# LNA.net
KiCad netlist of a schematic drawn in Altium Designer
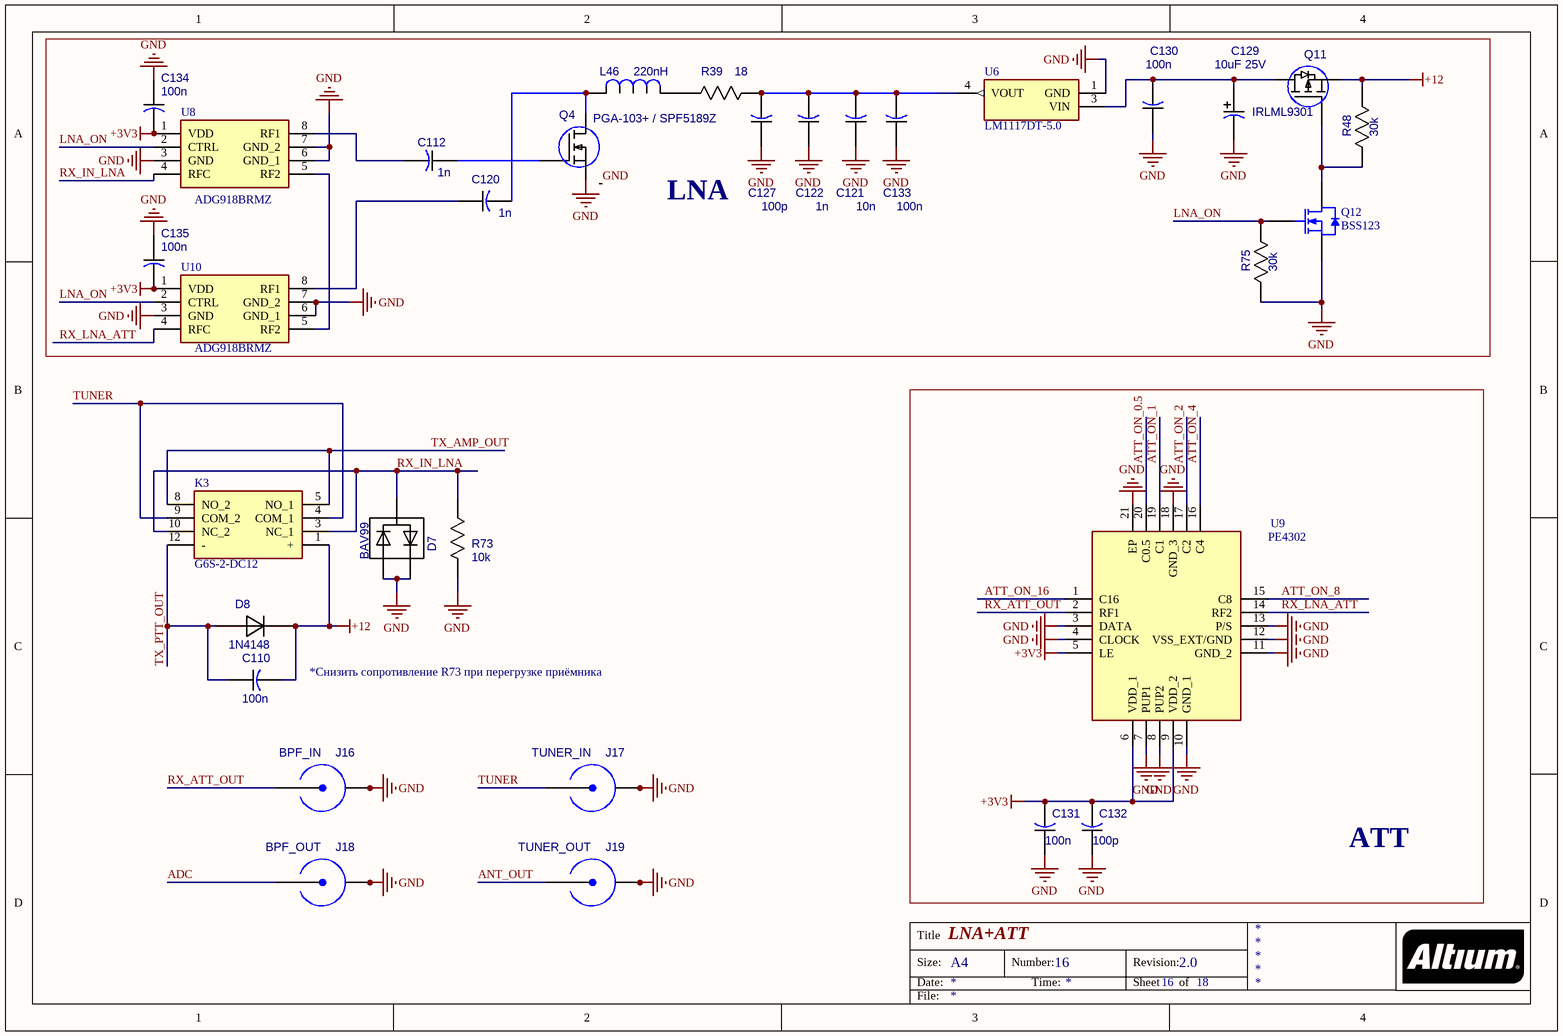
[diagram p0: LNA.SchDoc]

(export (version "E")
  (design (tool "Eeschema 10.0.6"))
  (components
    (comp (ref "C110")
      (value "100n")
      (footprint "CAP_0805")
      (description "CAP_0805")
      (libsource (lib "*") (part "CAP_0805"))
    )
    (comp (ref "C112")
      (value "1n")
      (footprint "CAP_0805")
      (description "CAP_0805")
      (libsource (lib "*") (part "CAP_0805"))
    )
    (comp (ref "C120")
      (value "1n")
      (footprint "CAP_0805")
      (description "CAP_0805")
      (libsource (lib "*") (part "CAP_0805"))
    )
    (comp (ref "C121")
      (value "10n")
      (footprint "6-0805_M")
      (description "CAP_0805")
      (libsource (lib "*") (part "CAP_0805"))
    )
    (comp (ref "C122")
      (value "1n")
      (footprint "6-0805_M")
      (description "CAP_0805")
      (libsource (lib "*") (part "CAP_0805"))
    )
    (comp (ref "C127")
      (value "100p")
      (footprint "6-0805_M")
      (description "CAP_0805")
      (libsource (lib "*") (part "CAP_0805"))
    )
    (comp (ref "C129")
      (value "10uF 25V")
      (footprint "CAPAE_5.3x5.3h6.1")
      (description "CAPAE_5.3x5.3h6.1")
      (libsource (lib "*") (part "CAPAE_5.3x5.3h6.1"))
    )
    (comp (ref "C130")
      (value "100n")
      (footprint "CAP_0805")
      (description "CAP_0805")
      (libsource (lib "") (part "CAP_0805_1"))
    )
    (comp (ref "C131")
      (value "100n")
      (footprint "6-0805_M")
      (description "CAP_0805")
      (libsource (lib "*") (part "CAP_0805"))
    )
    (comp (ref "C132")
      (value "100p")
      (footprint "6-0805_M")
      (description "CAP_0805")
      (libsource (lib "*") (part "CAP_0805"))
    )
    (comp (ref "C133")
      (value "100n")
      (footprint "CAP_0805")
      (description "CAP_0805")
      (libsource (lib "*") (part "CAP_0805"))
    )
    (comp (ref "C134")
      (value "100n")
      (footprint "CAP_0805")
      (description "CAP_0805")
      (libsource (lib "*") (part "CAP_0805"))
    )
    (comp (ref "C135")
      (value "100n")
      (footprint "CAP_0805")
      (description "CAP_0805")
      (libsource (lib "*") (part "CAP_0805"))
    )
    (comp (ref "D7") (value "BAV99") (footprint "SOT23") (libsource (lib "*") (part "BAV99")))
    (comp (ref "D8") (value "1N4148") (footprint "SS14") (libsource (lib "RF-UNIT-BIG") (part "1N4148")))
    (comp (ref "J16")
      (value "BPF_IN")
      (footprint "31-5431")
      (description "SMA")
      (libsource (lib "RF-UNIT_1") (part "31-5431"))
    )
    (comp (ref "J17")
      (value "TUNER_IN")
      (footprint "31-5431")
      (description "SMA")
      (libsource (lib "RF-UNIT_1") (part "31-5431"))
    )
    (comp (ref "J18")
      (value "BPF_OUT")
      (footprint "31-5431")
      (description "SMA")
      (libsource (lib "RF-UNIT_1") (part "31-5431"))
    )
    (comp (ref "J19")
      (value "TUNER_OUT")
      (footprint "31-5431")
      (description "SMA")
      (libsource (lib "RF-UNIT_1") (part "31-5431"))
    )
    (comp (ref "K3")
      (value "G6S-2-DC12")
      (footprint "G6S2DC12")
      (description "Relay or Contactor")
      (fields (field (name "MOUSER PART NUMBER") "653-G6S-2-DC12A"))
      (libsource (lib "*") (part "G6S-2-DC12"))
    )
    (comp (ref "L46")
      (value "220nH")
      (footprint "IND_1206")
      (description "IND_1206")
      (libsource (lib "*") (part "IND_1206"))
    )
    (comp (ref "Q4")
      (value "PGA-103+ / SPF5189Z")
      (footprint "SOT89")
      (libsource (lib "*") (part "PGA-103+"))
    )
    (comp (ref "Q11")
      (value "IRLML9301")
      (footprint "SOT23")
      (description "MOSFET")
      (libsource (lib "*") (part "MOSFET_ENH_PD"))
    )
    (comp (ref "Q12")
      (value "BSS123")
      (footprint "FAIR-SOT23-3_V")
      (fields (field (name "MANUFACTURER") "Fairchild"))
      (libsource (lib "Altium Content Vault") (part "NEMOS-GSD-3"))
    )
    (comp (ref "R39")
      (value "18")
      (footprint "RES_1206")
      (description "RES_1206")
      (libsource (lib "*") (part "RES_1206"))
    )
    (comp (ref "R48")
      (value "30k")
      (footprint "RES_0805")
      (description "RES_0805")
      (libsource (lib "*") (part "RES_0805"))
    )
    (comp (ref "R73")
      (value "10k")
      (footprint "RES_1206")
      (description "RES_1206")
      (libsource (lib "*") (part "RES_1206"))
    )
    (comp (ref "R75")
      (value "30k")
      (footprint "RES_0805")
      (description "RES_0805")
      (libsource (lib "*") (part "RES_0805"))
    )
    (comp (ref "U6")
      (value "LM1117DT-5.0")
      (footprint "SamacSys:TO228P991X238-3N")
      (description "Integrated Circuit")
      (fields
        (field (name "MANUFACTURER_PART_NUMBER") "LM1117DT-ADJ")
        (field (name "MOUSER PART NUMBER") "926-LM1117DT-ADJ")
      )
      (libsource (lib "*") (part "LM1117DT-ADJ"))
    )
    (comp (ref "U8")
      (value "ADG918BRMZ")
      (footprint "SOP65P490X110-8N")
      (description "Integrated Circuit")
      (fields (field (name "MOUSER PART NUMBER") "584-ADG918BRMZ") (field (name "RS PART NUMBER") "4969212P"))
      (libsource (lib "RF-UNIT-BIG") (part "ADG918BRMZ"))
    )
    (comp (ref "U9")
      (value "PE4302")
      (footprint "QFN50P400X400X90-21N")
      (description "Integrated Circuit")
      (fields (field (name "MANUFACTURER_PART_NUMBER") "PE4312C-Z"))
      (libsource (lib "RF-UNIT-BIG") (part "PE4312C-Z"))
    )
    (comp (ref "U10")
      (value "ADG918BRMZ")
      (footprint "SOP65P490X110-8N")
      (description "Integrated Circuit")
      (fields (field (name "MOUSER PART NUMBER") "584-ADG918BRMZ") (field (name "RS PART NUMBER") "4969212P"))
      (libsource (lib "RF-UNIT-BIG") (part "ADG918BRMZ"))
    )
  )
  (nets
    (net (code "1") (name "+3V3") (class "Default")
      (node (ref "C131") (pin "2") (pinfunction "2_2") (pintype "passive"))
      (node (ref "C132") (pin "2") (pinfunction "2_2") (pintype "passive"))
      (node (ref "C134") (pin "2") (pinfunction "2_2") (pintype "passive"))
      (node (ref "C135") (pin "2") (pinfunction "2_2") (pintype "passive"))
      (node (ref "U10") (pin "1") (pinfunction "VDD_1") (pintype "power_in"))
      (node (ref "U8") (pin "1") (pinfunction "VDD_1") (pintype "power_in"))
      (node (ref "U9") (pin "5") (pinfunction "LE_5") (pintype "passive"))
      (node (ref "U9") (pin "6") (pinfunction "VDD_1_6") (pintype "passive"))
      (node (ref "U9") (pin "9") (pinfunction "VDD_2_9") (pintype "passive"))
    )
    (net (code "2") (name "+12") (class "Default")
      (node (ref "C110") (pin "2") (pinfunction "2_2") (pintype "passive"))
      (node (ref "D8") (pin "1") (pinfunction "K_1") (pintype "passive"))
      (node (ref "K3") (pin "1") (pinfunction "+_1") (pintype "passive"))
      (node (ref "Q11") (pin "2") (pinfunction "S_2") (pintype "passive"))
      (node (ref "R48") (pin "2") (pinfunction "2_2") (pintype "passive"))
    )
    (net (code "3") (name "/ADC") (class "Default")
      (node (ref "J18") (pin "5") (pinfunction "CON_5") (pintype "passive"))
    )
    (net (code "4") (name "/ANT_OUT") (class "Default")
      (node (ref "J19") (pin "5") (pinfunction "CON_5") (pintype "passive"))
    )
    (net (code "5") (name "/ATT_ON_0.5") (class "Default")
      (node (ref "U9") (pin "20") (pinfunction "C0.5_20") (pintype "passive"))
    )
    (net (code "6") (name "/ATT_ON_1") (class "Default")
      (node (ref "U9") (pin "19") (pinfunction "C1_19") (pintype "passive"))
    )
    (net (code "7") (name "/ATT_ON_2") (class "Default")
      (node (ref "U9") (pin "17") (pinfunction "C2_17") (pintype "passive"))
    )
    (net (code "8") (name "/ATT_ON_4") (class "Default")
      (node (ref "U9") (pin "16") (pinfunction "C4_16") (pintype "passive"))
    )
    (net (code "9") (name "/ATT_ON_8") (class "Default")
      (node (ref "U9") (pin "15") (pinfunction "C8_15") (pintype "passive"))
    )
    (net (code "10") (name "/ATT_ON_16") (class "Default")
      (node (ref "U9") (pin "1") (pinfunction "C16_1") (pintype "passive"))
    )
    (net (code "11") (name "/LNA_ON") (class "Default")
      (node (ref "Q12") (pin "1") (pinfunction "G_1") (pintype "passive"))
      (node (ref "R75") (pin "2") (pinfunction "2_2") (pintype "passive"))
      (node (ref "U10") (pin "2") (pinfunction "CTRL_2") (pintype "passive"))
      (node (ref "U8") (pin "2") (pinfunction "CTRL_2") (pintype "passive"))
    )
    (net (code "12") (name "/RX_ATT_OUT") (class "Default")
      (node (ref "J16") (pin "5") (pinfunction "CON_5") (pintype "passive"))
      (node (ref "U9") (pin "2") (pinfunction "RF1_2") (pintype "passive"))
    )
    (net (code "13") (name "/RX_IN_LNA") (class "Default")
      (node (ref "D7") (pin "3") (pinfunction "C(D1),A(D2)_3") (pintype "passive"))
      (node (ref "K3") (pin "10") (pinfunction "NC_2_10") (pintype "passive"))
      (node (ref "K3") (pin "3") (pinfunction "NC_1_3") (pintype "passive"))
      (node (ref "R73") (pin "2") (pinfunction "2_2") (pintype "passive"))
      (node (ref "U8") (pin "4") (pinfunction "RFC_4") (pintype "passive"))
    )
    (net (code "14") (name "/RX_LNA_ATT") (class "Default")
      (node (ref "U10") (pin "4") (pinfunction "RFC_4") (pintype "passive"))
      (node (ref "U9") (pin "14") (pinfunction "RF2_14") (pintype "passive"))
    )
    (net (code "15") (name "/TUNER") (class "Default")
      (node (ref "J17") (pin "5") (pinfunction "CON_5") (pintype "passive"))
      (node (ref "K3") (pin "4") (pinfunction "COM_1_4") (pintype "passive"))
      (node (ref "K3") (pin "9") (pinfunction "COM_2_9") (pintype "passive"))
    )
    (net (code "16") (name "/TX_AMP_OUT") (class "Default")
      (node (ref "K3") (pin "5") (pinfunction "NO_1_5") (pintype "passive"))
      (node (ref "K3") (pin "8") (pinfunction "NO_2_8") (pintype "passive"))
    )
    (net (code "17") (name "/TX_PTT_OUT") (class "Default")
      (node (ref "C110") (pin "1") (pinfunction "1_1") (pintype "passive"))
      (node (ref "D8") (pin "2") (pinfunction "A_2") (pintype "passive"))
      (node (ref "K3") (pin "12") (pinfunction "-_12") (pintype "passive"))
    )
    (net (code "18") (name "GND") (class "Default")
      (node (ref "C121") (pin "1") (pinfunction "1_1") (pintype "passive"))
      (node (ref "C122") (pin "1") (pinfunction "1_1") (pintype "passive"))
      (node (ref "C127") (pin "1") (pinfunction "1_1") (pintype "passive"))
      (node (ref "C129") (pin "2") (pinfunction "MINUS_2") (pintype "passive"))
      (node (ref "C130") (pin "1") (pinfunction "1_1") (pintype "passive"))
      (node (ref "C131") (pin "1") (pinfunction "1_1") (pintype "passive"))
      (node (ref "C132") (pin "1") (pinfunction "1_1") (pintype "passive"))
      (node (ref "C133") (pin "1") (pinfunction "1_1") (pintype "passive"))
      (node (ref "C134") (pin "1") (pinfunction "1_1") (pintype "passive"))
      (node (ref "C135") (pin "1") (pinfunction "1_1") (pintype "passive"))
      (node (ref "D7") (pin "1") (pinfunction "A(D1)_1") (pintype "passive"))
      (node (ref "D7") (pin "2") (pinfunction "C(D2)_2") (pintype "passive"))
      (node (ref "J16") (pin "1") (pinfunction "GND_1") (pintype "passive"))
      (node (ref "J16") (pin "2") (pinfunction "GND_2") (pintype "passive"))
      (node (ref "J16") (pin "3") (pinfunction "GND_3") (pintype "passive"))
      (node (ref "J16") (pin "4") (pinfunction "GND_4") (pintype "passive"))
      (node (ref "J17") (pin "1") (pinfunction "GND_1") (pintype "passive"))
      (node (ref "J17") (pin "2") (pinfunction "GND_2") (pintype "passive"))
      (node (ref "J17") (pin "3") (pinfunction "GND_3") (pintype "passive"))
      (node (ref "J17") (pin "4") (pinfunction "GND_4") (pintype "passive"))
      (node (ref "J18") (pin "1") (pinfunction "GND_1") (pintype "passive"))
      (node (ref "J18") (pin "2") (pinfunction "GND_2") (pintype "passive"))
      (node (ref "J18") (pin "3") (pinfunction "GND_3") (pintype "passive"))
      (node (ref "J18") (pin "4") (pinfunction "GND_4") (pintype "passive"))
      (node (ref "J19") (pin "1") (pinfunction "GND_1") (pintype "passive"))
      (node (ref "J19") (pin "2") (pinfunction "GND_2") (pintype "passive"))
      (node (ref "J19") (pin "3") (pinfunction "GND_3") (pintype "passive"))
      (node (ref "J19") (pin "4") (pinfunction "GND_4") (pintype "passive"))
      (node (ref "Q12") (pin "2") (pinfunction "S_2") (pintype "passive"))
      (node (ref "Q4") (pin "0") (pinfunction "0_0") (pintype "passive"))
      (node (ref "Q4") (pin "2") (pinfunction "S_2") (pintype "passive"))
      (node (ref "R73") (pin "1") (pinfunction "1_1") (pintype "passive"))
      (node (ref "R75") (pin "1") (pinfunction "1_1") (pintype "passive"))
      (node (ref "U10") (pin "3") (pinfunction "GND_3") (pintype "power_in"))
      (node (ref "U10") (pin "6") (pinfunction "GND_1_6") (pintype "power_in"))
      (node (ref "U10") (pin "7") (pinfunction "GND_2_7") (pintype "power_in"))
      (node (ref "U6") (pin "1") (pinfunction "GND_1") (pintype "passive"))
      (node (ref "U8") (pin "3") (pinfunction "GND_3") (pintype "power_in"))
      (node (ref "U8") (pin "6") (pinfunction "GND_1_6") (pintype "power_in"))
      (node (ref "U8") (pin "7") (pinfunction "GND_2_7") (pintype "power_in"))
      (node (ref "U9") (pin "10") (pinfunction "GND_1_10") (pintype "passive"))
      (node (ref "U9") (pin "11") (pinfunction "GND_2_11") (pintype "passive"))
      (node (ref "U9") (pin "12") (pinfunction "VSS_EXT/GND_12") (pintype "passive"))
      (node (ref "U9") (pin "13") (pinfunction "P/S_13") (pintype "passive"))
      (node (ref "U9") (pin "18") (pinfunction "GND_3_18") (pintype "passive"))
      (node (ref "U9") (pin "21") (pinfunction "EP_21") (pintype "passive"))
      (node (ref "U9") (pin "3") (pinfunction "DATA_3") (pintype "passive"))
      (node (ref "U9") (pin "4") (pinfunction "CLOCK_4") (pintype "passive"))
      (node (ref "U9") (pin "7") (pinfunction "PUP1_7") (pintype "passive"))
      (node (ref "U9") (pin "8") (pinfunction "PUP2_8") (pintype "passive"))
    )
    (net (code "19") (name "Net-(C129-PLUS)") (class "Default")
      (node (ref "C129") (pin "1") (pinfunction "PLUS_1") (pintype "passive"))
      (node (ref "C130") (pin "2") (pinfunction "2_2") (pintype "passive"))
      (node (ref "Q11") (pin "3") (pinfunction "D_3") (pintype "passive"))
      (node (ref "U6") (pin "3") (pinfunction "VIN_3") (pintype "passive"))
    )
    (net (code "20") (name "Net-(L46-1)") (class "Default")
      (node (ref "C120") (pin "2") (pinfunction "2_2") (pintype "passive"))
      (node (ref "L46") (pin "2") (pinfunction "1_2") (pintype "passive"))
      (node (ref "Q4") (pin "3") (pinfunction "D_3") (pintype "passive"))
    )
    (net (code "21") (name "Net-(L46-2)") (class "Default")
      (node (ref "L46") (pin "1") (pinfunction "2_1") (pintype "passive"))
      (node (ref "R39") (pin "2") (pinfunction "2_2") (pintype "passive"))
    )
    (net (code "22") (name "Net-(Q4-G)") (class "Default")
      (node (ref "C112") (pin "1") (pinfunction "1_1") (pintype "passive"))
      (node (ref "Q4") (pin "1") (pinfunction "G_1") (pintype "passive"))
    )
    (net (code "23") (name "Net-(Q11-G)") (class "Default")
      (node (ref "Q11") (pin "1") (pinfunction "G_1") (pintype "passive"))
      (node (ref "Q12") (pin "3") (pinfunction "D_3") (pintype "passive"))
      (node (ref "R48") (pin "1") (pinfunction "1_1") (pintype "passive"))
    )
    (net (code "24") (name "Net-(U6-VOUT)") (class "Default")
      (node (ref "C121") (pin "2") (pinfunction "2_2") (pintype "passive"))
      (node (ref "C122") (pin "2") (pinfunction "2_2") (pintype "passive"))
      (node (ref "C127") (pin "2") (pinfunction "2_2") (pintype "passive"))
      (node (ref "C133") (pin "2") (pinfunction "2_2") (pintype "passive"))
      (node (ref "R39") (pin "1") (pinfunction "1_1") (pintype "passive"))
      (node (ref "U6") (pin "4") (pinfunction "VOUT_4") (pintype "output"))
    )
    (net (code "25") (name "Net-(U8-RF1)") (class "Default")
      (node (ref "C112") (pin "2") (pinfunction "2_2") (pintype "passive"))
      (node (ref "U8") (pin "8") (pinfunction "RF1_8") (pintype "passive"))
    )
    (net (code "26") (name "Net-(U10-RF1)") (class "Default")
      (node (ref "C120") (pin "1") (pinfunction "1_1") (pintype "passive"))
      (node (ref "U10") (pin "8") (pinfunction "RF1_8") (pintype "passive"))
    )
    (net (code "27") (name "Net-(U10-RF2)") (class "Default")
      (node (ref "U10") (pin "5") (pinfunction "RF2_5") (pintype "passive"))
      (node (ref "U8") (pin "5") (pinfunction "RF2_5") (pintype "passive"))
    )
  )
)
